# MPB_v1.net
KiCad netlist of a schematic drawn in EAGLE
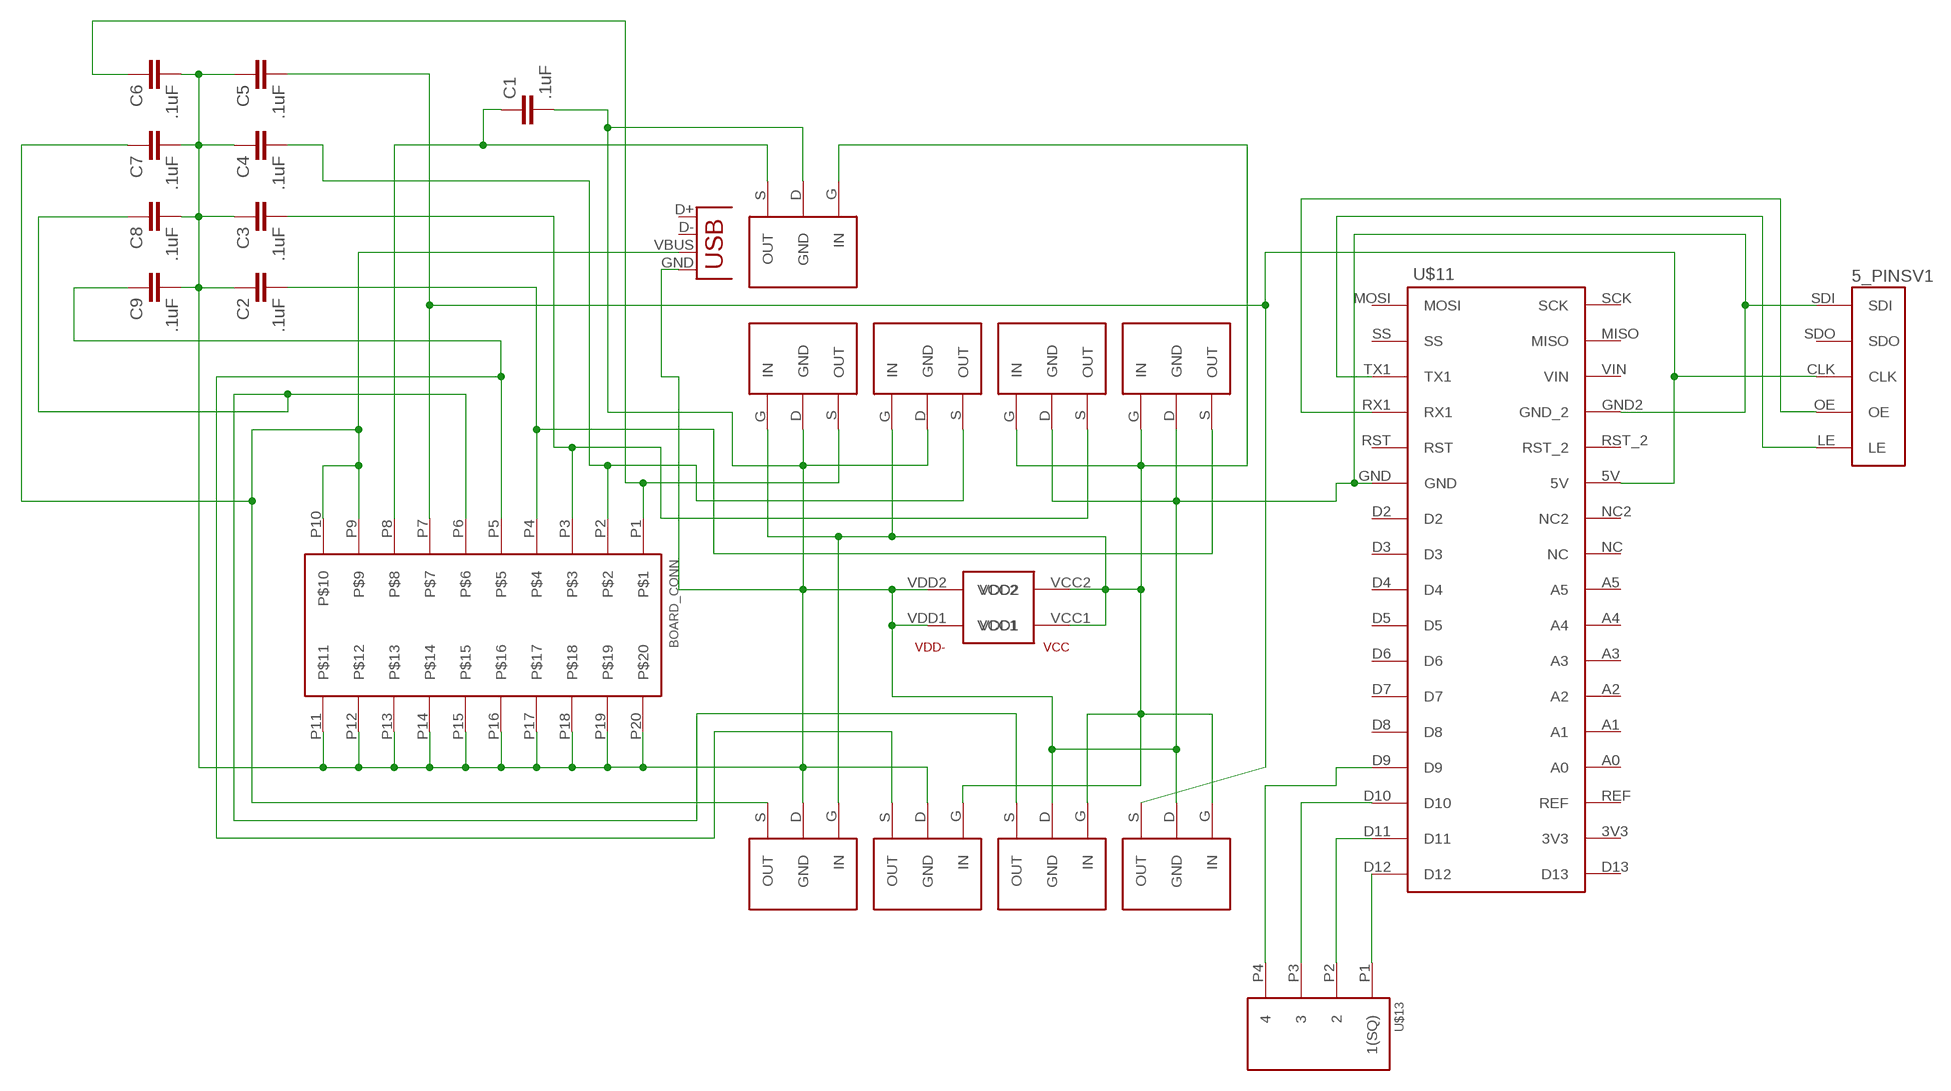
[diagram p0: schematic, sheet 1]

(export (version "E")
  (design (tool "Eeschema 10.0.6"))
  (components
    (comp (ref "BOARD_CONN")
      (value "20PIN_HEADER")
      (footprint "eagle-import:20PIN_3MMHEADER")
      (libsource (lib "eagle-import") (part "20PIN_HEADER"))
    )
    (comp (ref "C1")
      (value ".1uF")
      (footprint "eagle-import:CAP-PTH-SMALL-KIT")
      (libsource (lib "eagle-import") (part "0.1UF-50V-20%(PTH)KIT-EZ"))
    )
    (comp (ref "C2")
      (value ".1uF")
      (footprint "eagle-import:CAP-PTH-SMALL-KIT")
      (libsource (lib "eagle-import") (part "0.1UF-50V-20%(PTH)KIT-EZ"))
    )
    (comp (ref "C3")
      (value ".1uF")
      (footprint "eagle-import:CAP-PTH-SMALL-KIT")
      (libsource (lib "eagle-import") (part "0.1UF-50V-20%(PTH)KIT-EZ"))
    )
    (comp (ref "C4")
      (value ".1uF")
      (footprint "eagle-import:CAP-PTH-SMALL-KIT")
      (libsource (lib "eagle-import") (part "0.1UF-50V-20%(PTH)KIT-EZ"))
    )
    (comp (ref "C5")
      (value ".1uF")
      (footprint "eagle-import:CAP-PTH-SMALL-KIT")
      (libsource (lib "eagle-import") (part "0.1UF-50V-20%(PTH)KIT-EZ"))
    )
    (comp (ref "C6")
      (value ".1uF")
      (footprint "eagle-import:CAP-PTH-SMALL-KIT")
      (libsource (lib "eagle-import") (part "0.1UF-50V-20%(PTH)KIT-EZ"))
    )
    (comp (ref "C7")
      (value ".1uF")
      (footprint "eagle-import:CAP-PTH-SMALL-KIT")
      (libsource (lib "eagle-import") (part "0.1UF-50V-20%(PTH)KIT-EZ"))
    )
    (comp (ref "C8")
      (value ".1uF")
      (footprint "eagle-import:CAP-PTH-SMALL-KIT")
      (libsource (lib "eagle-import") (part "0.1UF-50V-20%(PTH)KIT-EZ"))
    )
    (comp (ref "C9")
      (value ".1uF")
      (footprint "eagle-import:CAP-PTH-SMALL-KIT")
      (libsource (lib "eagle-import") (part "0.1UF-50V-20%(PTH)KIT-EZ"))
    )
    (comp (ref "PWR")
      (value "4PIN_POWER")
      (footprint "eagle-import:KPJX-4S")
      (libsource (lib "eagle-import") (part "4PIN_POWER"))
    )
    (comp (ref "R1")
      (value "5VREG")
      (footprint "eagle-import:TO220BH")
      (libsource (lib "eagle-import") (part "5VREG"))
    )
    (comp (ref "R2")
      (value "5VREG")
      (footprint "eagle-import:TO220BH")
      (libsource (lib "eagle-import") (part "5VREG"))
    )
    (comp (ref "R3")
      (value "5VREG")
      (footprint "eagle-import:TO220BH")
      (libsource (lib "eagle-import") (part "5VREG"))
    )
    (comp (ref "R4")
      (value "5VREG")
      (footprint "eagle-import:TO220BH")
      (libsource (lib "eagle-import") (part "5VREG"))
    )
    (comp (ref "R5")
      (value "5VREG")
      (footprint "eagle-import:TO220BH")
      (libsource (lib "eagle-import") (part "5VREG"))
    )
    (comp (ref "R6")
      (value "5VREG")
      (footprint "eagle-import:TO220BH")
      (libsource (lib "eagle-import") (part "5VREG"))
    )
    (comp (ref "R7")
      (value "5VREG")
      (footprint "eagle-import:TO220BH")
      (libsource (lib "eagle-import") (part "5VREG"))
    )
    (comp (ref "R8")
      (value "5VREG")
      (footprint "eagle-import:TO220BH")
      (libsource (lib "eagle-import") (part "5VREG"))
    )
    (comp (ref "R9")
      (value "5VREG")
      (footprint "eagle-import:TO220BH")
      (libsource (lib "eagle-import") (part "5VREG"))
    )
    (comp (ref "U$11")
      (value "ARDUINOMICRO1")
      (footprint "eagle-import:ARDUINOMICRO")
      (libsource (lib "eagle-import") (part "ARDUINOMICRO1"))
    )
    (comp (ref "U$12")
      (value "5_PINSV1")
      (footprint "eagle-import:5PIN_HOLES")
      (libsource (lib "eagle-import") (part "5_PINSV1"))
    )
    (comp (ref "U$13")
      (value "4_PINS1")
      (footprint "eagle-import:4PIN_HOLES")
      (libsource (lib "eagle-import") (part "4_PINS1"))
    )
    (comp (ref "_")
      (value "USB-A-SMD")
      (footprint "eagle-import:USB-A-S-NOSILK-FEMALE")
      (libsource (lib "eagle-import") (part "USB-A-SMD"))
    )
  )
  (nets
    (net (code "1") (name "Net-(BOARD_CONN-P$1)") (class "Default")
      (node (ref "BOARD_CONN") (pin "P1") (pinfunction "P$1_P1") (pintype "bidirectional"))
      (node (ref "C6") (pin "1") (pinfunction "1_1") (pintype "passive"))
      (node (ref "R9") (pin "S") (pinfunction "OUT_S") (pintype "bidirectional"))
    )
    (net (code "2") (name "Net-(BOARD_CONN-P$2)") (class "Default")
      (node (ref "BOARD_CONN") (pin "P2") (pinfunction "P$2_P2") (pintype "bidirectional"))
      (node (ref "C4") (pin "2") (pinfunction "2_2") (pintype "passive"))
      (node (ref "R1") (pin "S") (pinfunction "OUT_S") (pintype "bidirectional"))
    )
    (net (code "3") (name "Net-(BOARD_CONN-P$3)") (class "Default")
      (node (ref "BOARD_CONN") (pin "P3") (pinfunction "P$3_P3") (pintype "bidirectional"))
      (node (ref "C3") (pin "2") (pinfunction "2_2") (pintype "passive"))
      (node (ref "R3") (pin "S") (pinfunction "OUT_S") (pintype "bidirectional"))
    )
    (net (code "4") (name "Net-(BOARD_CONN-P$4)") (class "Default")
      (node (ref "BOARD_CONN") (pin "P4") (pinfunction "P$4_P4") (pintype "bidirectional"))
      (node (ref "C2") (pin "2") (pinfunction "2_2") (pintype "passive"))
      (node (ref "R2") (pin "S") (pinfunction "OUT_S") (pintype "bidirectional"))
    )
    (net (code "5") (name "Net-(BOARD_CONN-P$5)") (class "Default")
      (node (ref "BOARD_CONN") (pin "P5") (pinfunction "P$5_P5") (pintype "bidirectional"))
      (node (ref "C9") (pin "1") (pinfunction "1_1") (pintype "passive"))
      (node (ref "R6") (pin "S") (pinfunction "OUT_S") (pintype "bidirectional"))
    )
    (net (code "6") (name "Net-(BOARD_CONN-P$6)") (class "Default")
      (node (ref "BOARD_CONN") (pin "P6") (pinfunction "P$6_P6") (pintype "bidirectional"))
      (node (ref "C8") (pin "1") (pinfunction "1_1") (pintype "passive"))
      (node (ref "R8") (pin "S") (pinfunction "OUT_S") (pintype "bidirectional"))
    )
    (net (code "7") (name "Net-(BOARD_CONN-P$7)") (class "Default")
      (node (ref "BOARD_CONN") (pin "P7") (pinfunction "P$7_P7") (pintype "bidirectional"))
      (node (ref "C5") (pin "2") (pinfunction "2_2") (pintype "passive"))
      (node (ref "R4") (pin "S") (pinfunction "OUT_S") (pintype "bidirectional"))
      (node (ref "U$11") (pin "5V") (pinfunction "5V_5V") (pintype "bidirectional"))
      (node (ref "U$12") (pin "CLK") (pinfunction "CLK_CLK") (pintype "bidirectional"))
    )
    (net (code "8") (name "Net-(BOARD_CONN-P$8)") (class "Default")
      (node (ref "BOARD_CONN") (pin "P8") (pinfunction "P$8_P8") (pintype "bidirectional"))
      (node (ref "C1") (pin "1") (pinfunction "1_1") (pintype "passive"))
      (node (ref "R7") (pin "S") (pinfunction "OUT_S") (pintype "bidirectional"))
    )
    (net (code "9") (name "Net-(BOARD_CONN-P$10)") (class "Default")
      (node (ref "BOARD_CONN") (pin "P10") (pinfunction "P$10_P10") (pintype "bidirectional"))
      (node (ref "BOARD_CONN") (pin "P9") (pinfunction "P$9_P9") (pintype "bidirectional"))
      (node (ref "C7") (pin "1") (pinfunction "1_1") (pintype "passive"))
      (node (ref "R5") (pin "S") (pinfunction "OUT_S") (pintype "bidirectional"))
      (node (ref "_") (pin "VBUS") (pinfunction "VBUS_VBUS") (pintype "bidirectional"))
    )
    (net (code "10") (name "Net-(BOARD_CONN-P$11)") (class "Default")
      (node (ref "BOARD_CONN") (pin "P11") (pinfunction "P$11_P11") (pintype "bidirectional"))
      (node (ref "BOARD_CONN") (pin "P12") (pinfunction "P$12_P12") (pintype "bidirectional"))
      (node (ref "BOARD_CONN") (pin "P13") (pinfunction "P$13_P13") (pintype "bidirectional"))
      (node (ref "BOARD_CONN") (pin "P14") (pinfunction "P$14_P14") (pintype "bidirectional"))
      (node (ref "BOARD_CONN") (pin "P15") (pinfunction "P$15_P15") (pintype "bidirectional"))
      (node (ref "BOARD_CONN") (pin "P16") (pinfunction "P$16_P16") (pintype "bidirectional"))
      (node (ref "BOARD_CONN") (pin "P17") (pinfunction "P$17_P17") (pintype "bidirectional"))
      (node (ref "BOARD_CONN") (pin "P18") (pinfunction "P$18_P18") (pintype "bidirectional"))
      (node (ref "BOARD_CONN") (pin "P19") (pinfunction "P$19_P19") (pintype "bidirectional"))
      (node (ref "BOARD_CONN") (pin "P20") (pinfunction "P$20_P20") (pintype "bidirectional"))
      (node (ref "C1") (pin "2") (pinfunction "2_2") (pintype "passive"))
      (node (ref "C2") (pin "1") (pinfunction "1_1") (pintype "passive"))
      (node (ref "C3") (pin "1") (pinfunction "1_1") (pintype "passive"))
      (node (ref "C4") (pin "1") (pinfunction "1_1") (pintype "passive"))
      (node (ref "C5") (pin "1") (pinfunction "1_1") (pintype "passive"))
      (node (ref "C6") (pin "2") (pinfunction "2_2") (pintype "passive"))
      (node (ref "C7") (pin "2") (pinfunction "2_2") (pintype "passive"))
      (node (ref "C8") (pin "2") (pinfunction "2_2") (pintype "passive"))
      (node (ref "C9") (pin "2") (pinfunction "2_2") (pintype "passive"))
      (node (ref "PWR") (pin "VDD1") (pinfunction "VDD1_VDD1") (pintype "bidirectional"))
      (node (ref "PWR") (pin "VDD2") (pinfunction "VDD2_VDD2") (pintype "bidirectional"))
      (node (ref "R1") (pin "D") (pinfunction "GND_D") (pintype "bidirectional"))
      (node (ref "R2") (pin "D") (pinfunction "GND_D") (pintype "bidirectional"))
      (node (ref "R3") (pin "D") (pinfunction "GND_D") (pintype "bidirectional"))
      (node (ref "R4") (pin "D") (pinfunction "GND_D") (pintype "bidirectional"))
      (node (ref "R5") (pin "D") (pinfunction "GND_D") (pintype "bidirectional"))
      (node (ref "R6") (pin "D") (pinfunction "GND_D") (pintype "bidirectional"))
      (node (ref "R7") (pin "D") (pinfunction "GND_D") (pintype "bidirectional"))
      (node (ref "R8") (pin "D") (pinfunction "GND_D") (pintype "bidirectional"))
      (node (ref "R9") (pin "D") (pinfunction "GND_D") (pintype "bidirectional"))
      (node (ref "U$11") (pin "GND") (pinfunction "GND_GND") (pintype "bidirectional"))
      (node (ref "U$11") (pin "GND2") (pinfunction "GND_2_GND2") (pintype "bidirectional"))
      (node (ref "U$12") (pin "SDI") (pinfunction "SDI_SDI") (pintype "bidirectional"))
      (node (ref "_") (pin "GND") (pinfunction "GND_GND") (pintype "bidirectional"))
    )
    (net (code "11") (name "Net-(R1-IN)") (class "Default")
      (node (ref "PWR") (pin "VCC1") (pinfunction "VCC1_VCC1") (pintype "bidirectional"))
      (node (ref "PWR") (pin "VCC2") (pinfunction "VCC2_VCC2") (pintype "bidirectional"))
      (node (ref "R1") (pin "G") (pinfunction "IN_G") (pintype "bidirectional"))
      (node (ref "R2") (pin "G") (pinfunction "IN_G") (pintype "bidirectional"))
      (node (ref "R3") (pin "G") (pinfunction "IN_G") (pintype "bidirectional"))
      (node (ref "R4") (pin "G") (pinfunction "IN_G") (pintype "bidirectional"))
      (node (ref "R5") (pin "G") (pinfunction "IN_G") (pintype "bidirectional"))
      (node (ref "R6") (pin "G") (pinfunction "IN_G") (pintype "bidirectional"))
      (node (ref "R7") (pin "G") (pinfunction "IN_G") (pintype "bidirectional"))
      (node (ref "R8") (pin "G") (pinfunction "IN_G") (pintype "bidirectional"))
      (node (ref "R9") (pin "G") (pinfunction "IN_G") (pintype "bidirectional"))
    )
    (net (code "12") (name "Net-(U$11-PadRX1)") (class "Default")
      (node (ref "U$11") (pin "RX1") (pinfunction "RX1_RX1") (pintype "bidirectional"))
      (node (ref "U$12") (pin "OE") (pinfunction "OE_OE") (pintype "bidirectional"))
    )
    (net (code "13") (name "Net-(U$11-PadTX1)") (class "Default")
      (node (ref "U$11") (pin "TX1") (pinfunction "TX1_TX1") (pintype "bidirectional"))
      (node (ref "U$12") (pin "LE") (pinfunction "LE_LE") (pintype "bidirectional"))
    )
    (net (code "14") (name "Net-(U$13-1(SQ))") (class "Default")
      (node (ref "U$11") (pin "D12") (pinfunction "D12_D12") (pintype "bidirectional"))
      (node (ref "U$13") (pin "P1") (pinfunction "1(SQ)_P1") (pintype "bidirectional"))
    )
    (net (code "15") (name "Net-(U$13-2)") (class "Default")
      (node (ref "U$11") (pin "D11") (pinfunction "D11_D11") (pintype "bidirectional"))
      (node (ref "U$13") (pin "P2") (pinfunction "2_P2") (pintype "bidirectional"))
    )
    (net (code "16") (name "Net-(U$13-3)") (class "Default")
      (node (ref "U$11") (pin "D10") (pinfunction "D10_D10") (pintype "bidirectional"))
      (node (ref "U$13") (pin "P3") (pinfunction "3_P3") (pintype "bidirectional"))
    )
    (net (code "17") (name "Net-(U$13-4)") (class "Default")
      (node (ref "U$11") (pin "D9") (pinfunction "D9_D9") (pintype "bidirectional"))
      (node (ref "U$13") (pin "P4") (pinfunction "4_P4") (pintype "bidirectional"))
    )
    (net (code "18") (name "unconnected-(U$11-Pad3V3)") (class "Default")
      (node (ref "U$11") (pin "3V3") (pinfunction "3V3_3V3") (pintype "bidirectional"))
    )
    (net (code "19") (name "unconnected-(U$11-PadA0)") (class "Default")
      (node (ref "U$11") (pin "A0") (pinfunction "A0_A0") (pintype "bidirectional"))
    )
    (net (code "20") (name "unconnected-(U$11-PadA1)") (class "Default")
      (node (ref "U$11") (pin "A1") (pinfunction "A1_A1") (pintype "bidirectional"))
    )
    (net (code "21") (name "unconnected-(U$11-PadA2)") (class "Default")
      (node (ref "U$11") (pin "A2") (pinfunction "A2_A2") (pintype "bidirectional"))
    )
    (net (code "22") (name "unconnected-(U$11-PadA3)") (class "Default")
      (node (ref "U$11") (pin "A3") (pinfunction "A3_A3") (pintype "bidirectional"))
    )
    (net (code "23") (name "unconnected-(U$11-PadA4)") (class "Default")
      (node (ref "U$11") (pin "A4") (pinfunction "A4_A4") (pintype "bidirectional"))
    )
    (net (code "24") (name "unconnected-(U$11-PadA5)") (class "Default")
      (node (ref "U$11") (pin "A5") (pinfunction "A5_A5") (pintype "bidirectional"))
    )
    (net (code "25") (name "unconnected-(U$11-PadD2)") (class "Default")
      (node (ref "U$11") (pin "D2") (pinfunction "D2_D2") (pintype "bidirectional"))
    )
    (net (code "26") (name "unconnected-(U$11-PadD3)") (class "Default")
      (node (ref "U$11") (pin "D3") (pinfunction "D3_D3") (pintype "bidirectional"))
    )
    (net (code "27") (name "unconnected-(U$11-PadD4)") (class "Default")
      (node (ref "U$11") (pin "D4") (pinfunction "D4_D4") (pintype "bidirectional"))
    )
    (net (code "28") (name "unconnected-(U$11-PadD5)") (class "Default")
      (node (ref "U$11") (pin "D5") (pinfunction "D5_D5") (pintype "bidirectional"))
    )
    (net (code "29") (name "unconnected-(U$11-PadD6)") (class "Default")
      (node (ref "U$11") (pin "D6") (pinfunction "D6_D6") (pintype "bidirectional"))
    )
    (net (code "30") (name "unconnected-(U$11-PadD7)") (class "Default")
      (node (ref "U$11") (pin "D7") (pinfunction "D7_D7") (pintype "bidirectional"))
    )
    (net (code "31") (name "unconnected-(U$11-PadD8)") (class "Default")
      (node (ref "U$11") (pin "D8") (pinfunction "D8_D8") (pintype "bidirectional"))
    )
    (net (code "32") (name "unconnected-(U$11-PadD13)") (class "Default")
      (node (ref "U$11") (pin "D13") (pinfunction "D13_D13") (pintype "bidirectional"))
    )
    (net (code "33") (name "unconnected-(U$11-PadMISO)") (class "Default")
      (node (ref "U$11") (pin "MISO") (pinfunction "MISO_MISO") (pintype "bidirectional"))
    )
    (net (code "34") (name "unconnected-(U$11-PadMOSI)") (class "Default")
      (node (ref "U$11") (pin "MOSI") (pinfunction "MOSI_MOSI") (pintype "bidirectional"))
    )
    (net (code "35") (name "unconnected-(U$11-PadNC)") (class "Default")
      (node (ref "U$11") (pin "NC") (pinfunction "NC_NC") (pintype "bidirectional"))
    )
    (net (code "36") (name "unconnected-(U$11-PadNC2)") (class "Default")
      (node (ref "U$11") (pin "NC2") (pinfunction "NC2_NC2") (pintype "bidirectional"))
    )
    (net (code "37") (name "unconnected-(U$11-PadREF)") (class "Default")
      (node (ref "U$11") (pin "REF") (pinfunction "REF_REF") (pintype "bidirectional"))
    )
    (net (code "38") (name "unconnected-(U$11-PadRST)") (class "Default")
      (node (ref "U$11") (pin "RST") (pinfunction "RST_RST") (pintype "bidirectional"))
    )
    (net (code "39") (name "unconnected-(U$11-PadRST_2)") (class "Default")
      (node (ref "U$11") (pin "RST_2") (pinfunction "RST_2_RST_2") (pintype "bidirectional"))
    )
    (net (code "40") (name "unconnected-(U$11-PadSCK)") (class "Default")
      (node (ref "U$11") (pin "SCK") (pinfunction "SCK_SCK") (pintype "bidirectional"))
    )
    (net (code "41") (name "unconnected-(U$11-PadSS)") (class "Default")
      (node (ref "U$11") (pin "SS") (pinfunction "SS_SS") (pintype "bidirectional"))
    )
    (net (code "42") (name "unconnected-(U$11-PadVIN)") (class "Default")
      (node (ref "U$11") (pin "VIN") (pinfunction "VIN_VIN") (pintype "bidirectional"))
    )
    (net (code "43") (name "unconnected-(U$12-PadSDO)") (class "Default")
      (node (ref "U$12") (pin "SDO") (pinfunction "SDO_SDO") (pintype "bidirectional"))
    )
    (net (code "44") (name "unconnected-(_-PadD+)") (class "Default")
      (node (ref "_") (pin "D+") (pinfunction "D+_D+") (pintype "bidirectional"))
    )
    (net (code "45") (name "unconnected-(_-PadD-)") (class "Default")
      (node (ref "_") (pin "D-") (pinfunction "D-_D-") (pintype "bidirectional"))
    )
  )
)
